# USB_HUB_EASYEDA.net
KiCad netlist of a schematic drawn in EasyEDA Pro
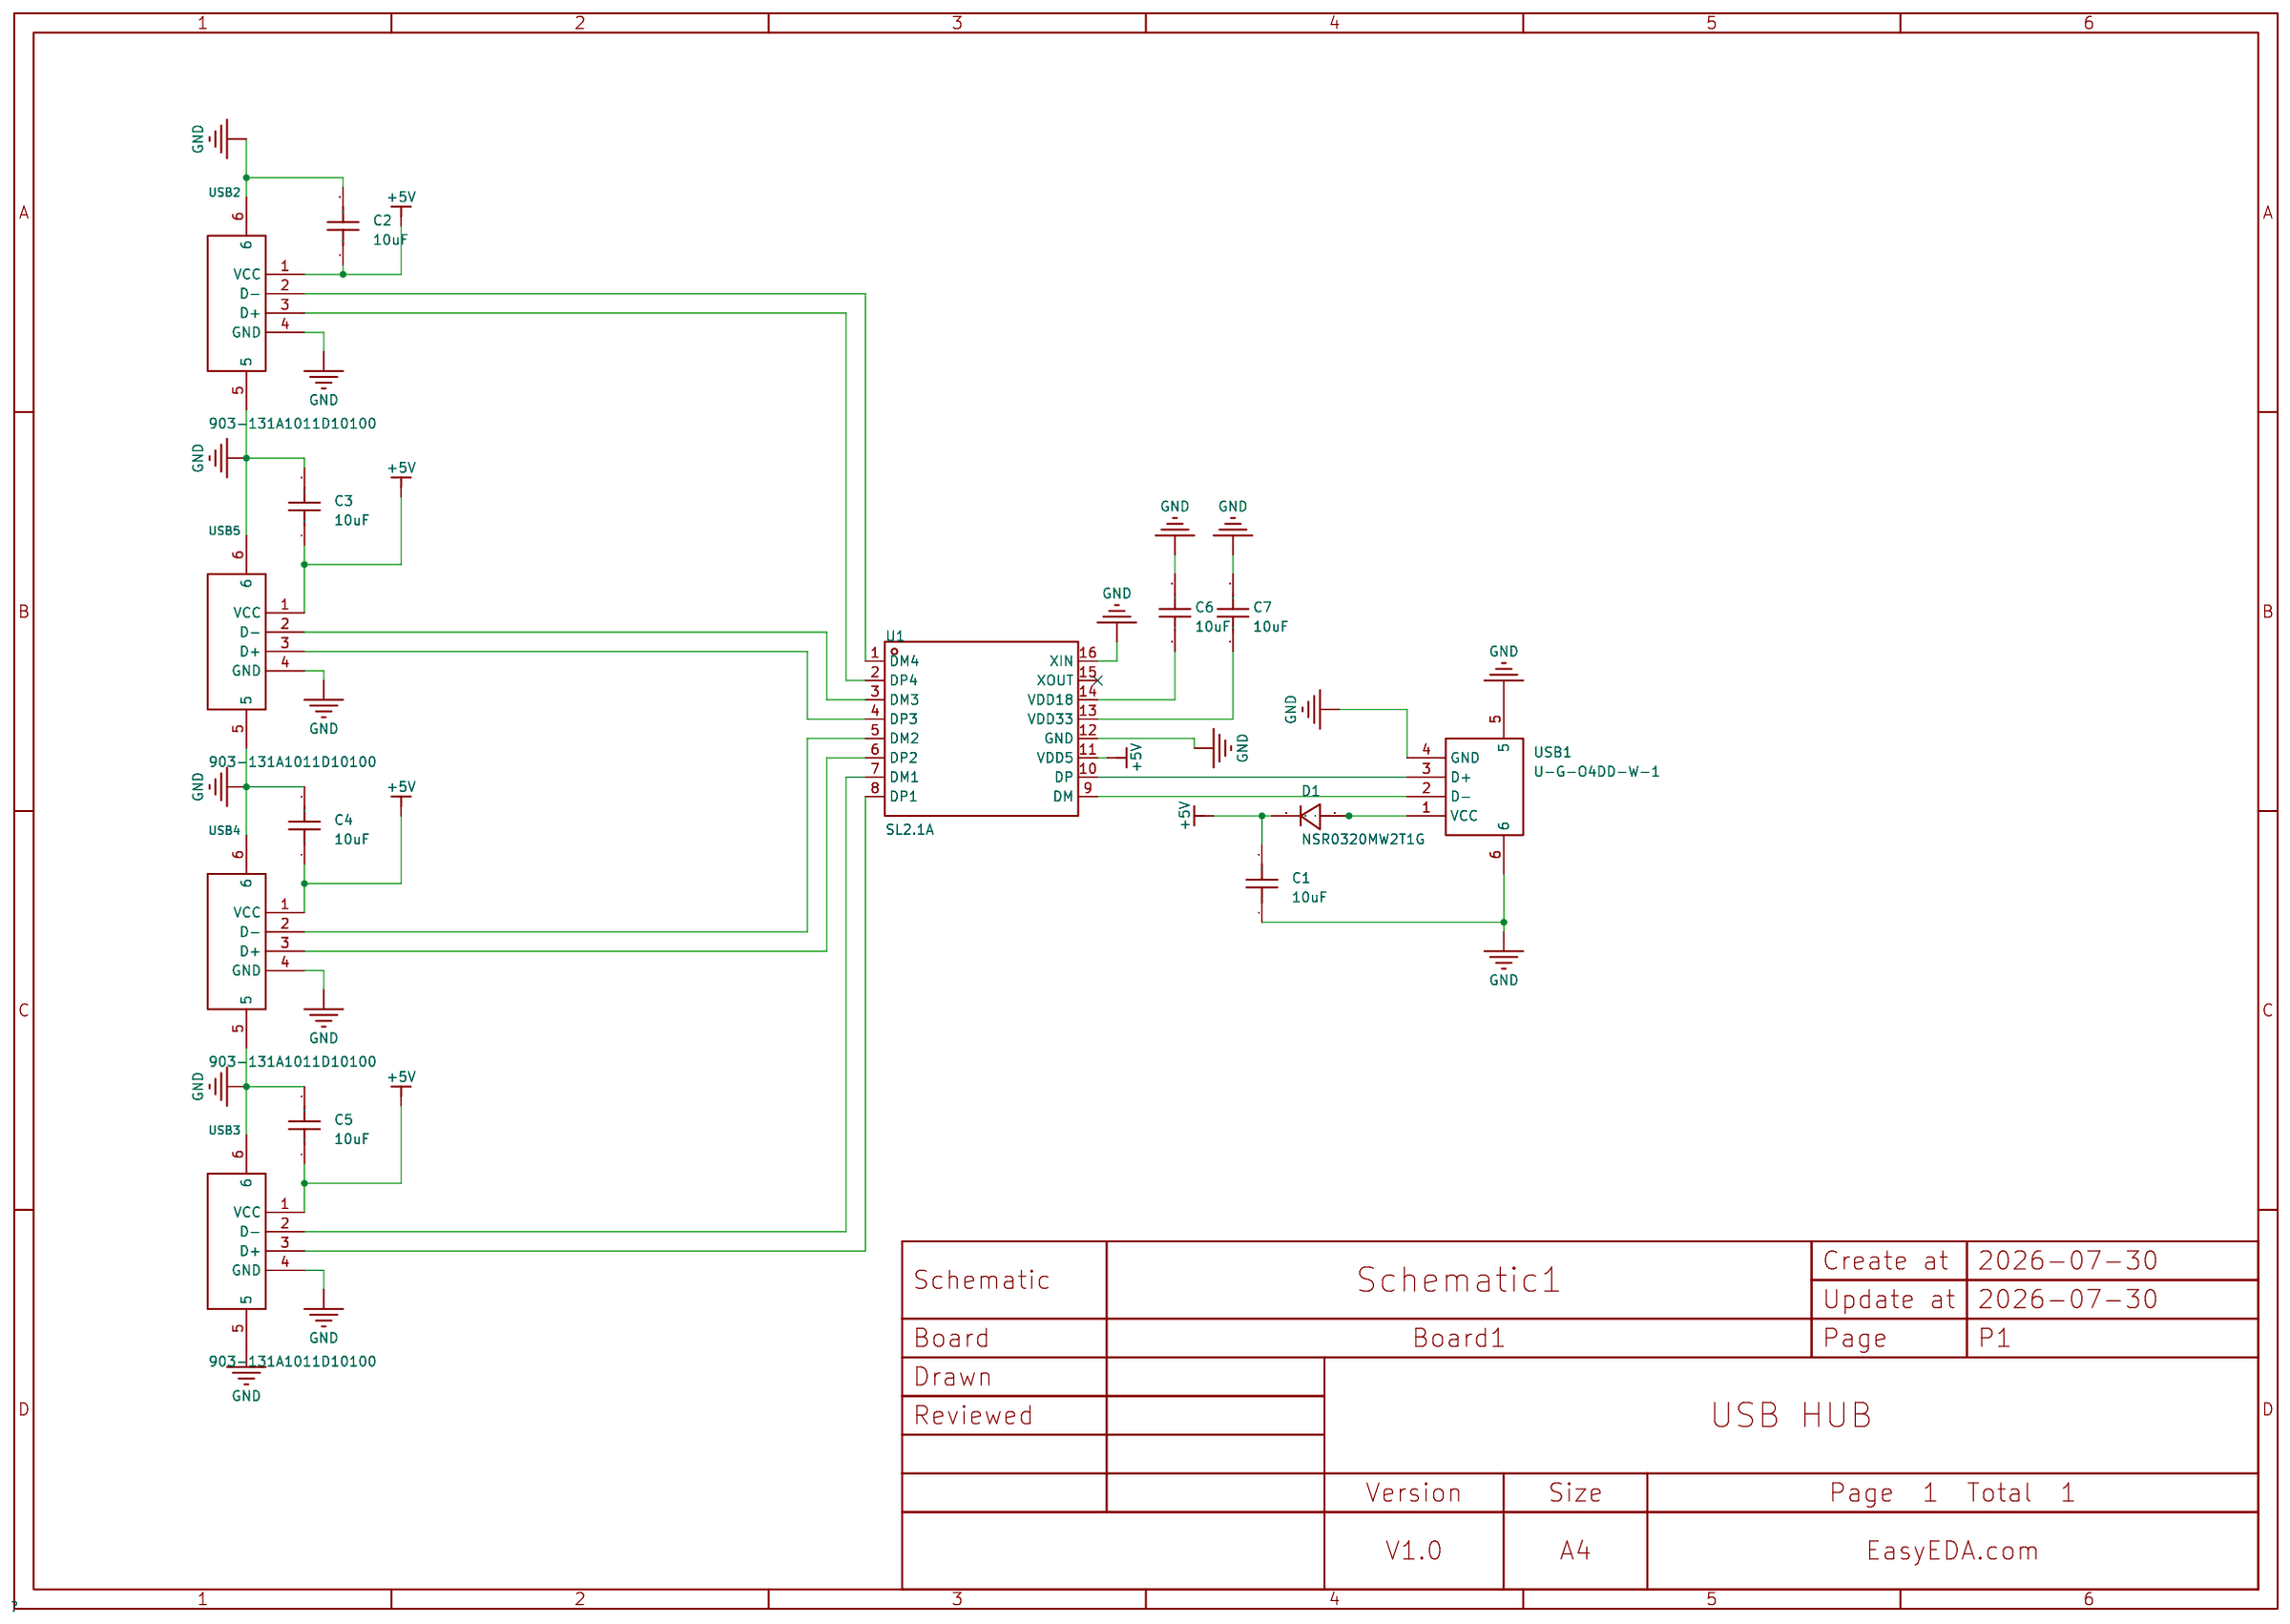
[diagram p0: schematic sheet]

(export (version "E")
  (design (tool "Eeschema 10.0.6"))
  (components
    (comp (ref "C1")
      (value "10uF")
      (footprint "easyedapro:C0603")
      (fields
        (field (name "Manufacturer Part") "CL10A106KP8NNNC")
        (field (name "Manufacturer") "SAMSUNG(三星)")
      )
      (libsource (lib "easyedapro") (part "CL10A106KP8NNNC"))
    )
    (comp (ref "C2")
      (value "10uF")
      (footprint "easyedapro:C0603")
      (fields
        (field (name "Manufacturer Part") "CL10A106KP8NNNC")
        (field (name "Manufacturer") "SAMSUNG(三星)")
      )
      (libsource (lib "easyedapro") (part "CL10A106KP8NNNC"))
    )
    (comp (ref "C3")
      (value "10uF")
      (footprint "easyedapro:C0603")
      (description "Capacitance:10uF Tolerance:±10% Tolerance:±10% Voltage Rating:10V Temperature Coefficient:X5R")
      (fields
        (field (name "Manufacturer Part") "CL10A106KP8NNNC")
        (field (name "Manufacturer") "SAMSUNG(三星)")
      )
      (libsource (lib "easyedapro") (part "CL10A106KP8NNNC"))
    )
    (comp (ref "C4")
      (value "10uF")
      (footprint "easyedapro:C0603")
      (description "Capacitance:10uF Tolerance:±10% Tolerance:±10% Voltage Rating:10V Temperature Coefficient:X5R")
      (fields
        (field (name "Manufacturer Part") "CL10A106KP8NNNC")
        (field (name "Manufacturer") "SAMSUNG(三星)")
      )
      (libsource (lib "easyedapro") (part "CL10A106KP8NNNC"))
    )
    (comp (ref "C5")
      (value "10uF")
      (footprint "easyedapro:C0603")
      (description "Capacitance:10uF Tolerance:±10% Tolerance:±10% Voltage Rating:10V Temperature Coefficient:X5R")
      (fields
        (field (name "Manufacturer Part") "CL10A106KP8NNNC")
        (field (name "Manufacturer") "SAMSUNG(三星)")
      )
      (libsource (lib "easyedapro") (part "CL10A106KP8NNNC"))
    )
    (comp (ref "C6")
      (value "10uF")
      (footprint "easyedapro:C0603")
      (description "Capacitance:10uF Tolerance:±10% Tolerance:±10% Voltage Rating:10V Temperature Coefficient:X5R")
      (fields
        (field (name "Manufacturer Part") "CL10A106KP8NNNC")
        (field (name "Manufacturer") "SAMSUNG(三星)")
      )
      (libsource (lib "easyedapro") (part "CL10A106KP8NNNC"))
    )
    (comp (ref "C7")
      (value "10uF")
      (footprint "easyedapro:C0603")
      (description "Capacitance:10uF Tolerance:±10% Tolerance:±10% Voltage Rating:10V Temperature Coefficient:X5R")
      (fields
        (field (name "Manufacturer Part") "CL10A106KP8NNNC")
        (field (name "Manufacturer") "SAMSUNG(三星)")
      )
      (libsource (lib "easyedapro") (part "CL10A106KP8NNNC"))
    )
    (comp (ref "D1")
      (value "NSR0320MW2T1G")
      (footprint "easyedapro:SOD-323_L1.8-W1.3-LS2.5-RD")
      (fields (field (name "Manufacturer") "onsemi(安森美)"))
      (libsource (lib "easyedapro") (part "NSR0320MW2T1G"))
    )
    (comp (ref "U1")
      (value "SL2.1A")
      (footprint "easyedapro:SOP-16_L10.0-W3.9-P1.27-LS6.0-BL")
      (fields (field (name "Manufacturer") "CoreChips(和芯润德)"))
      (libsource (lib "easyedapro") (part "SL2.1A"))
    )
    (comp (ref "USB1")
      (value "U-G-O4DD-W-1")
      (footprint "easyedapro:USB-A-TH_U-G-04WD-W-01")
      (fields (field (name "Manufacturer") "韩国韩荣"))
      (libsource (lib "easyedapro") (part "U-G-04DD-W-01"))
    )
    (comp (ref "USB2")
      (value "903-131A1011D10100")
      (footprint "easyedapro:USB-A-TH_C46407")
      (fields (field (name "Manufacturer") "精拓金"))
      (libsource (lib "easyedapro") (part "USB-AF-90-14.4X13.6-H7.0-DIP"))
    )
    (comp (ref "USB3")
      (value "903-131A1011D10100")
      (footprint "easyedapro:USB-A-TH_C46407")
      (fields (field (name "Manufacturer") "精拓金"))
      (libsource (lib "easyedapro") (part "USB-AF-90-14.4X13.6-H7.0-DIP"))
    )
    (comp (ref "USB4")
      (value "903-131A1011D10100")
      (footprint "easyedapro:USB-A-TH_C46407")
      (fields (field (name "Manufacturer") "精拓金"))
      (libsource (lib "easyedapro") (part "USB-AF-90-14.4X13.6-H7.0-DIP"))
    )
    (comp (ref "USB5")
      (value "903-131A1011D10100")
      (footprint "easyedapro:USB-A-TH_C46407")
      (fields (field (name "Manufacturer") "精拓金"))
      (libsource (lib "easyedapro") (part "USB-AF-90-14.4X13.6-H7.0-DIP"))
    )
  )
  (nets
    (net (code "1") (name "+5V") (class "Default")
      (node (ref "C1") (pin "2") (pinfunction "2_2") (pintype "unspecified"))
      (node (ref "C2") (pin "1") (pinfunction "1_1") (pintype "unspecified"))
      (node (ref "C3") (pin "1") (pinfunction "1_1") (pintype "unspecified"))
      (node (ref "C4") (pin "1") (pinfunction "1_1") (pintype "unspecified"))
      (node (ref "C5") (pin "1") (pinfunction "1_1") (pintype "unspecified"))
      (node (ref "D1") (pin "1") (pinfunction "C_1") (pintype "unspecified"))
      (node (ref "U1") (pin "11") (pinfunction "VDD5_11") (pintype "unspecified"))
      (node (ref "USB2") (pin "1") (pinfunction "VCC_1") (pintype "input"))
      (node (ref "USB3") (pin "1") (pinfunction "VCC_1") (pintype "input"))
      (node (ref "USB4") (pin "1") (pinfunction "VCC_1") (pintype "input"))
      (node (ref "USB5") (pin "1") (pinfunction "VCC_1") (pintype "input"))
    )
    (net (code "2") (name "GND") (class "Default")
      (node (ref "C1") (pin "1") (pinfunction "1_1") (pintype "unspecified"))
      (node (ref "C2") (pin "2") (pinfunction "2_2") (pintype "unspecified"))
      (node (ref "C3") (pin "2") (pinfunction "2_2") (pintype "unspecified"))
      (node (ref "C4") (pin "2") (pinfunction "2_2") (pintype "unspecified"))
      (node (ref "C5") (pin "2") (pinfunction "2_2") (pintype "unspecified"))
      (node (ref "C6") (pin "2") (pinfunction "2_2") (pintype "unspecified"))
      (node (ref "C7") (pin "2") (pinfunction "2_2") (pintype "unspecified"))
      (node (ref "U1") (pin "12") (pinfunction "GND_12") (pintype "unspecified"))
      (node (ref "U1") (pin "16") (pinfunction "XIN_16") (pintype "unspecified"))
      (node (ref "USB1") (pin "4") (pinfunction "GND_4") (pintype "unspecified"))
      (node (ref "USB1") (pin "5") (pinfunction "5_5") (pintype "unspecified"))
      (node (ref "USB1") (pin "6") (pinfunction "6_6") (pintype "unspecified"))
      (node (ref "USB2") (pin "4") (pinfunction "GND_4") (pintype "input"))
      (node (ref "USB2") (pin "5") (pinfunction "5_5") (pintype "input"))
      (node (ref "USB2") (pin "6") (pinfunction "6_6") (pintype "input"))
      (node (ref "USB3") (pin "4") (pinfunction "GND_4") (pintype "input"))
      (node (ref "USB3") (pin "5") (pinfunction "5_5") (pintype "input"))
      (node (ref "USB3") (pin "6") (pinfunction "6_6") (pintype "input"))
      (node (ref "USB4") (pin "4") (pinfunction "GND_4") (pintype "input"))
      (node (ref "USB4") (pin "5") (pinfunction "5_5") (pintype "input"))
      (node (ref "USB4") (pin "6") (pinfunction "6_6") (pintype "input"))
      (node (ref "USB5") (pin "4") (pinfunction "GND_4") (pintype "input"))
      (node (ref "USB5") (pin "5") (pinfunction "5_5") (pintype "input"))
      (node (ref "USB5") (pin "6") (pinfunction "6_6") (pintype "input"))
    )
    (net (code "3") (name "Net-(D1-A)") (class "Default")
      (node (ref "D1") (pin "2") (pinfunction "A_2") (pintype "unspecified"))
      (node (ref "USB1") (pin "1") (pinfunction "VCC_1") (pintype "unspecified"))
    )
    (net (code "4") (name "Net-(U1-DM)") (class "Default")
      (node (ref "U1") (pin "9") (pinfunction "DM_9") (pintype "unspecified"))
      (node (ref "USB1") (pin "2") (pinfunction "D-_2") (pintype "unspecified"))
    )
    (net (code "5") (name "Net-(U1-DM1)") (class "Default")
      (node (ref "U1") (pin "7") (pinfunction "DM1_7") (pintype "unspecified"))
      (node (ref "USB3") (pin "2") (pinfunction "D-_2") (pintype "input"))
    )
    (net (code "6") (name "Net-(U1-DM2)") (class "Default")
      (node (ref "U1") (pin "5") (pinfunction "DM2_5") (pintype "unspecified"))
      (node (ref "USB4") (pin "2") (pinfunction "D-_2") (pintype "input"))
    )
    (net (code "7") (name "Net-(U1-DM3)") (class "Default")
      (node (ref "U1") (pin "3") (pinfunction "DM3_3") (pintype "unspecified"))
      (node (ref "USB5") (pin "2") (pinfunction "D-_2") (pintype "input"))
    )
    (net (code "8") (name "Net-(U1-DM4)") (class "Default")
      (node (ref "U1") (pin "1") (pinfunction "DM4_1") (pintype "unspecified"))
      (node (ref "USB2") (pin "2") (pinfunction "D-_2") (pintype "input"))
    )
    (net (code "9") (name "Net-(U1-DP)") (class "Default")
      (node (ref "U1") (pin "10") (pinfunction "DP_10") (pintype "unspecified"))
      (node (ref "USB1") (pin "3") (pinfunction "D+_3") (pintype "unspecified"))
    )
    (net (code "10") (name "Net-(U1-DP1)") (class "Default")
      (node (ref "U1") (pin "8") (pinfunction "DP1_8") (pintype "unspecified"))
      (node (ref "USB3") (pin "3") (pinfunction "D+_3") (pintype "input"))
    )
    (net (code "11") (name "Net-(U1-DP2)") (class "Default")
      (node (ref "U1") (pin "6") (pinfunction "DP2_6") (pintype "unspecified"))
      (node (ref "USB4") (pin "3") (pinfunction "D+_3") (pintype "input"))
    )
    (net (code "12") (name "Net-(U1-DP3)") (class "Default")
      (node (ref "U1") (pin "4") (pinfunction "DP3_4") (pintype "unspecified"))
      (node (ref "USB5") (pin "3") (pinfunction "D+_3") (pintype "input"))
    )
    (net (code "13") (name "Net-(U1-DP4)") (class "Default")
      (node (ref "U1") (pin "2") (pinfunction "DP4_2") (pintype "unspecified"))
      (node (ref "USB2") (pin "3") (pinfunction "D+_3") (pintype "input"))
    )
    (net (code "14") (name "Net-(U1-VDD18)") (class "Default")
      (node (ref "C6") (pin "1") (pinfunction "1_1") (pintype "unspecified"))
      (node (ref "U1") (pin "14") (pinfunction "VDD18_14") (pintype "unspecified"))
    )
    (net (code "15") (name "Net-(U1-VDD33)") (class "Default")
      (node (ref "C7") (pin "1") (pinfunction "1_1") (pintype "unspecified"))
      (node (ref "U1") (pin "13") (pinfunction "VDD33_13") (pintype "unspecified"))
    )
    (net (code "16") (name "unconnected-(U1-XOUT-Pad15)") (class "Default")
      (node (ref "U1") (pin "15") (pinfunction "XOUT_15") (pintype "unspecified+no_connect"))
    )
  )
)
